# Raspberry_Pi4.net
KiCad netlist of a schematic drawn in Altium Designer
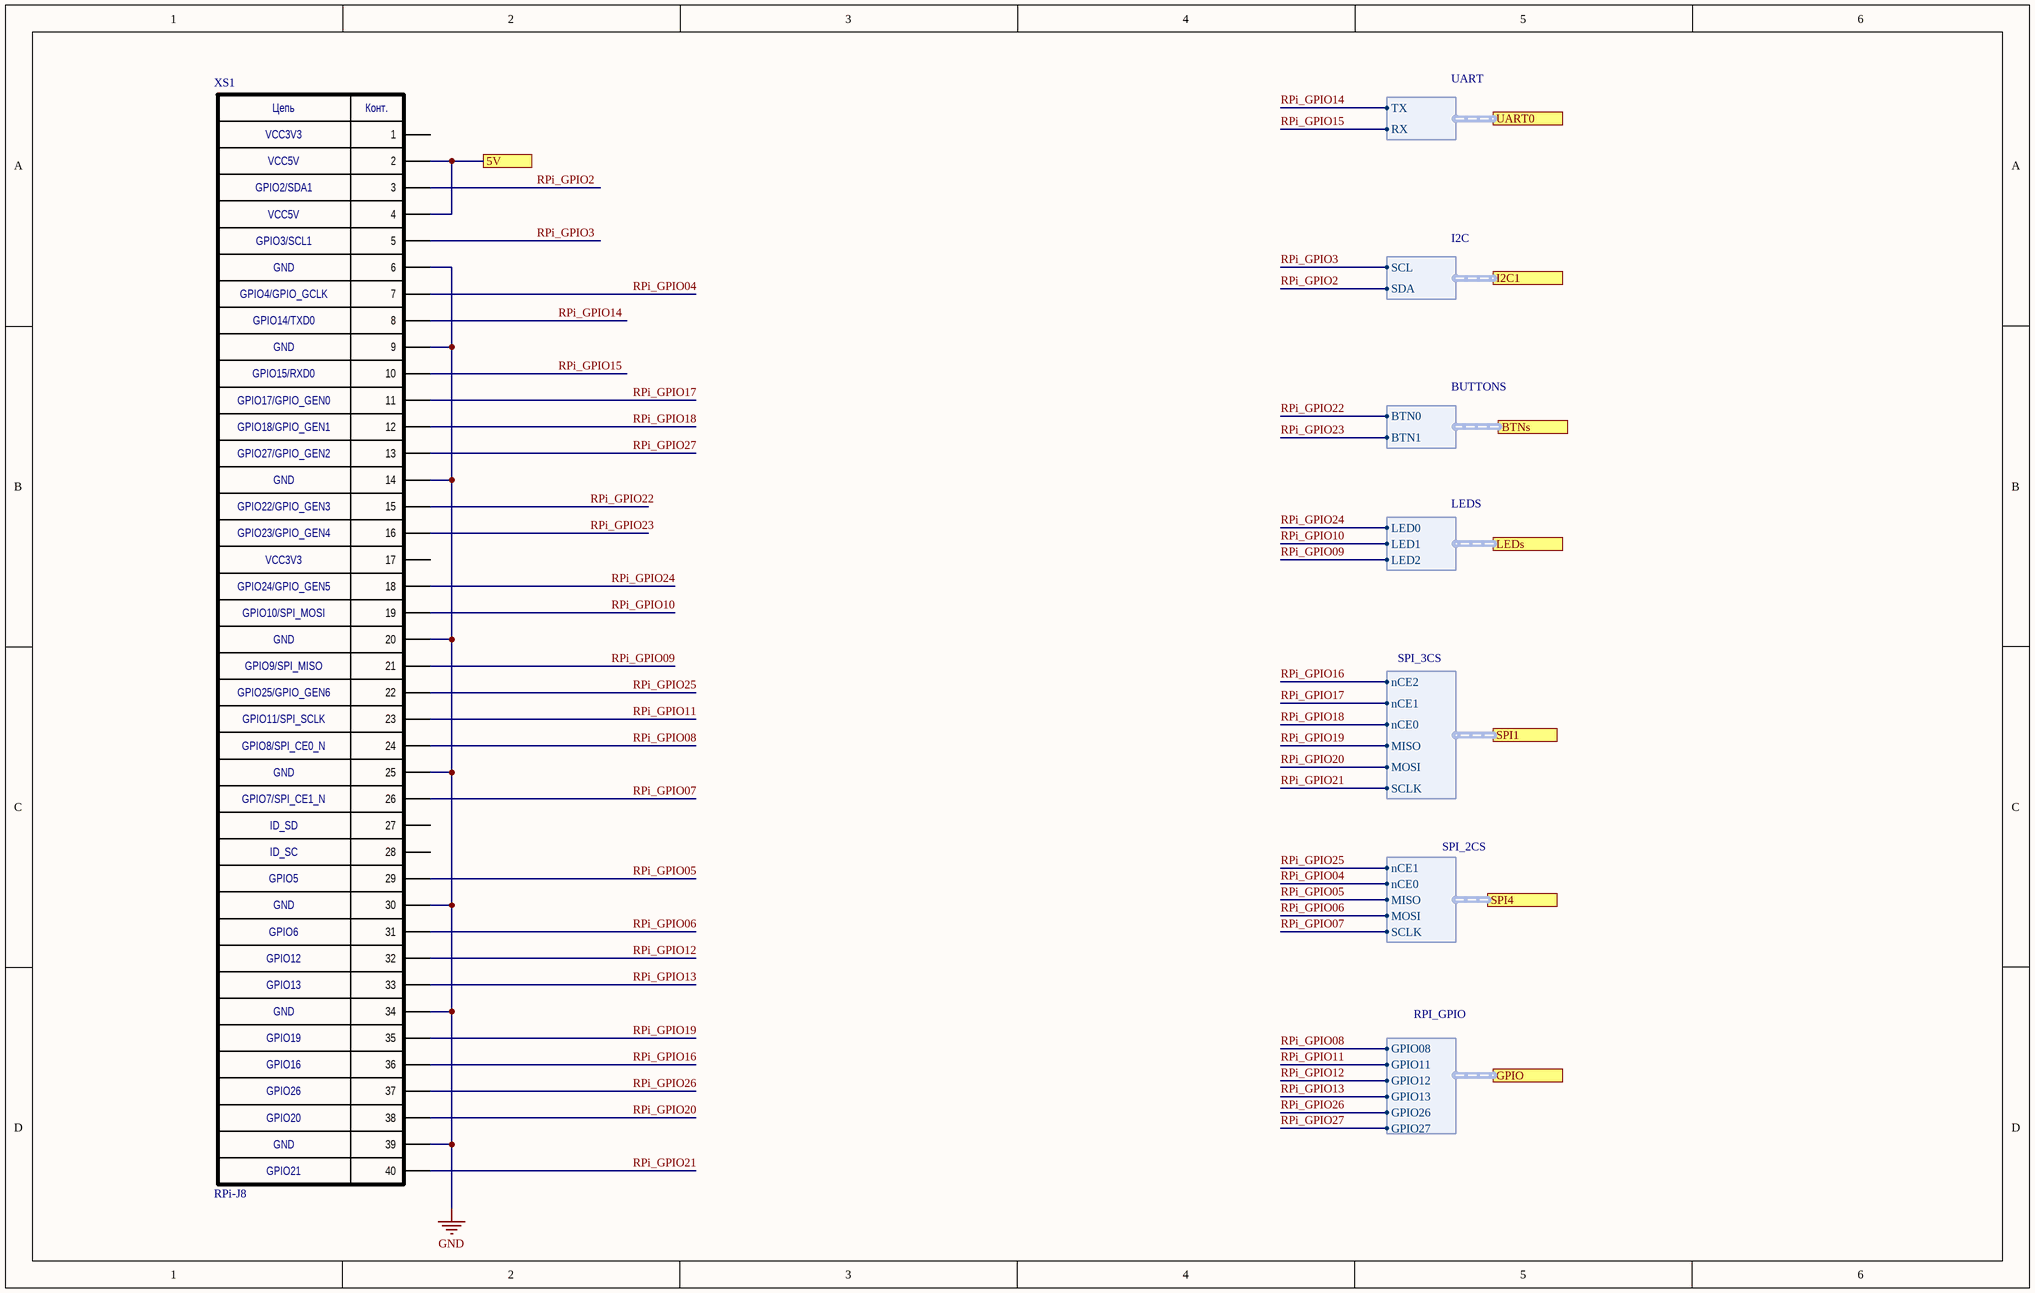
[diagram p0: Raspberry_Pi4.SchDoc]

(export (version "E")
  (design (tool "Eeschema 10.0.6"))
  (components
    (comp (ref "XS1")
      (value "RPi-J8")
      (footprint "RaPi_PLD-40")
      (fields
        (field (name "40") "GPIO21")
        (field (name "39") "GND")
        (field (name "38") "GPIO20")
        (field (name "37") "GPIO26")
        (field (name "36") "GPIO16")
        (field (name "35") "GPIO19")
        (field (name "34") "GND")
        (field (name "33") "GPIO13")
        (field (name "32") "GPIO12")
        (field (name "31") "GPIO6")
        (field (name "30") "GND")
        (field (name "29") "GPIO5")
        (field (name "28") "ID_SC")
        (field (name "27") "ID_SD")
        (field (name "26") "GPIO7/SPI_CE1_N")
        (field (name "25") "GND")
        (field (name "24") "GPIO8/SPI_CE0_N")
        (field (name "23") "GPIO11/SPI_SCLK")
        (field (name "22") "GPIO25/GPIO_GEN6")
        (field (name "21") "GPIO9/SPI_MISO")
        (field (name "20") "GND")
        (field (name "19") "GPIO10/SPI_MOSI")
        (field (name "18") "GPIO24/GPIO_GEN5")
        (field (name "17") "VCC3V3")
        (field (name "16") "GPIO23/GPIO_GEN4")
        (field (name "15") "GPIO22/GPIO_GEN3")
        (field (name "14") "GND")
        (field (name "13") "GPIO27/GPIO_GEN2")
        (field (name "9") "GND")
        (field (name "8") "GPIO14/TXD0")
        (field (name "7") "GPIO4/GPIO_GCLK")
        (field (name "12") "GPIO18/GPIO_GEN1")
        (field (name "5") "GPIO3/SCL1")
        (field (name "4") "VCC5V")
        (field (name "3") "GPIO2/SDA1")
        (field (name "2") "VCC5V")
        (field (name "6") "GND")
        (field (name "11") "GPIO17/GPIO_GEN0")
        (field (name "10") "GPIO15/RXD0")
        (field (name "1") "VCC3V3")
      )
      (libsource (lib "my_AP_lib_sch") (part "RPi-J8"))
    )
  )
  (nets
    (net (code "8") (name "/5V") (class "Default")
      (node (ref "XS1") (pin "2") (pinfunction "2_2") (pintype "passive"))
      (node (ref "XS1") (pin "4") (pinfunction "4_4") (pintype "passive"))
    )
    (net (code "9") (name "/RPi_GPIO2") (class "Default")
      (node (ref "XS1") (pin "3") (pinfunction "3_3") (pintype "passive"))
    )
    (net (code "10") (name "/RPi_GPIO3") (class "Default")
      (node (ref "XS1") (pin "5") (pinfunction "5_5") (pintype "passive"))
    )
    (net (code "11") (name "/RPi_GPIO04") (class "Default")
      (node (ref "XS1") (pin "7") (pinfunction "7_7") (pintype "passive"))
    )
    (net (code "12") (name "/RPi_GPIO05") (class "Default")
      (node (ref "XS1") (pin "29") (pinfunction "29_29") (pintype "passive"))
    )
    (net (code "13") (name "/RPi_GPIO06") (class "Default")
      (node (ref "XS1") (pin "31") (pinfunction "31_31") (pintype "passive"))
    )
    (net (code "14") (name "/RPi_GPIO07") (class "Default")
      (node (ref "XS1") (pin "26") (pinfunction "26_26") (pintype "passive"))
    )
    (net (code "15") (name "/RPi_GPIO08") (class "Default")
      (node (ref "XS1") (pin "24") (pinfunction "24_24") (pintype "passive"))
    )
    (net (code "16") (name "/RPi_GPIO09") (class "Default")
      (node (ref "XS1") (pin "21") (pinfunction "21_21") (pintype "passive"))
    )
    (net (code "17") (name "/RPi_GPIO10") (class "Default")
      (node (ref "XS1") (pin "19") (pinfunction "19_19") (pintype "passive"))
    )
    (net (code "18") (name "/RPi_GPIO11") (class "Default")
      (node (ref "XS1") (pin "23") (pinfunction "23_23") (pintype "passive"))
    )
    (net (code "19") (name "/RPi_GPIO12") (class "Default")
      (node (ref "XS1") (pin "32") (pinfunction "32_32") (pintype "passive"))
    )
    (net (code "20") (name "/RPi_GPIO13") (class "Default")
      (node (ref "XS1") (pin "33") (pinfunction "33_33") (pintype "passive"))
    )
    (net (code "21") (name "/RPi_GPIO14") (class "Default")
      (node (ref "XS1") (pin "8") (pinfunction "8_8") (pintype "passive"))
    )
    (net (code "22") (name "/RPi_GPIO15") (class "Default")
      (node (ref "XS1") (pin "10") (pinfunction "10_10") (pintype "passive"))
    )
    (net (code "23") (name "/RPi_GPIO16") (class "Default")
      (node (ref "XS1") (pin "36") (pinfunction "36_36") (pintype "passive"))
    )
    (net (code "24") (name "/RPi_GPIO17") (class "Default")
      (node (ref "XS1") (pin "11") (pinfunction "11_11") (pintype "passive"))
    )
    (net (code "25") (name "/RPi_GPIO18") (class "Default")
      (node (ref "XS1") (pin "12") (pinfunction "12_12") (pintype "passive"))
    )
    (net (code "26") (name "/RPi_GPIO19") (class "Default")
      (node (ref "XS1") (pin "35") (pinfunction "35_35") (pintype "passive"))
    )
    (net (code "27") (name "/RPi_GPIO20") (class "Default")
      (node (ref "XS1") (pin "38") (pinfunction "38_38") (pintype "passive"))
    )
    (net (code "28") (name "/RPi_GPIO21") (class "Default")
      (node (ref "XS1") (pin "40") (pinfunction "40_40") (pintype "passive"))
    )
    (net (code "29") (name "/RPi_GPIO22") (class "Default")
      (node (ref "XS1") (pin "15") (pinfunction "15_15") (pintype "passive"))
    )
    (net (code "30") (name "/RPi_GPIO23") (class "Default")
      (node (ref "XS1") (pin "16") (pinfunction "16_16") (pintype "passive"))
    )
    (net (code "31") (name "/RPi_GPIO24") (class "Default")
      (node (ref "XS1") (pin "18") (pinfunction "18_18") (pintype "passive"))
    )
    (net (code "32") (name "/RPi_GPIO25") (class "Default")
      (node (ref "XS1") (pin "22") (pinfunction "22_22") (pintype "passive"))
    )
    (net (code "33") (name "/RPi_GPIO26") (class "Default")
      (node (ref "XS1") (pin "37") (pinfunction "37_37") (pintype "passive"))
    )
    (net (code "34") (name "/RPi_GPIO27") (class "Default")
      (node (ref "XS1") (pin "13") (pinfunction "13_13") (pintype "passive"))
    )
    (net (code "42") (name "GND") (class "Default")
      (node (ref "XS1") (pin "14") (pinfunction "14_14") (pintype "passive"))
      (node (ref "XS1") (pin "20") (pinfunction "20_20") (pintype "passive"))
      (node (ref "XS1") (pin "25") (pinfunction "25_25") (pintype "passive"))
      (node (ref "XS1") (pin "30") (pinfunction "30_30") (pintype "passive"))
      (node (ref "XS1") (pin "34") (pinfunction "34_34") (pintype "passive"))
      (node (ref "XS1") (pin "39") (pinfunction "39_39") (pintype "passive"))
      (node (ref "XS1") (pin "6") (pinfunction "6_6") (pintype "passive"))
      (node (ref "XS1") (pin "9") (pinfunction "9_9") (pintype "passive"))
    )
    (net (code "43") (name "unconnected-(XS1-Pad1)") (class "Default")
      (node (ref "XS1") (pin "1") (pinfunction "1_1") (pintype "passive"))
    )
    (net (code "44") (name "unconnected-(XS1-Pad17)") (class "Default")
      (node (ref "XS1") (pin "17") (pinfunction "17_17") (pintype "passive"))
    )
    (net (code "45") (name "unconnected-(XS1-Pad27)") (class "Default")
      (node (ref "XS1") (pin "27") (pinfunction "27_27") (pintype "passive"))
    )
    (net (code "46") (name "unconnected-(XS1-Pad28)") (class "Default")
      (node (ref "XS1") (pin "28") (pinfunction "28_28") (pintype "passive"))
    )
  )
)
